# MainBoard_RASP.net
KiCad netlist of a schematic drawn in Altium Designer
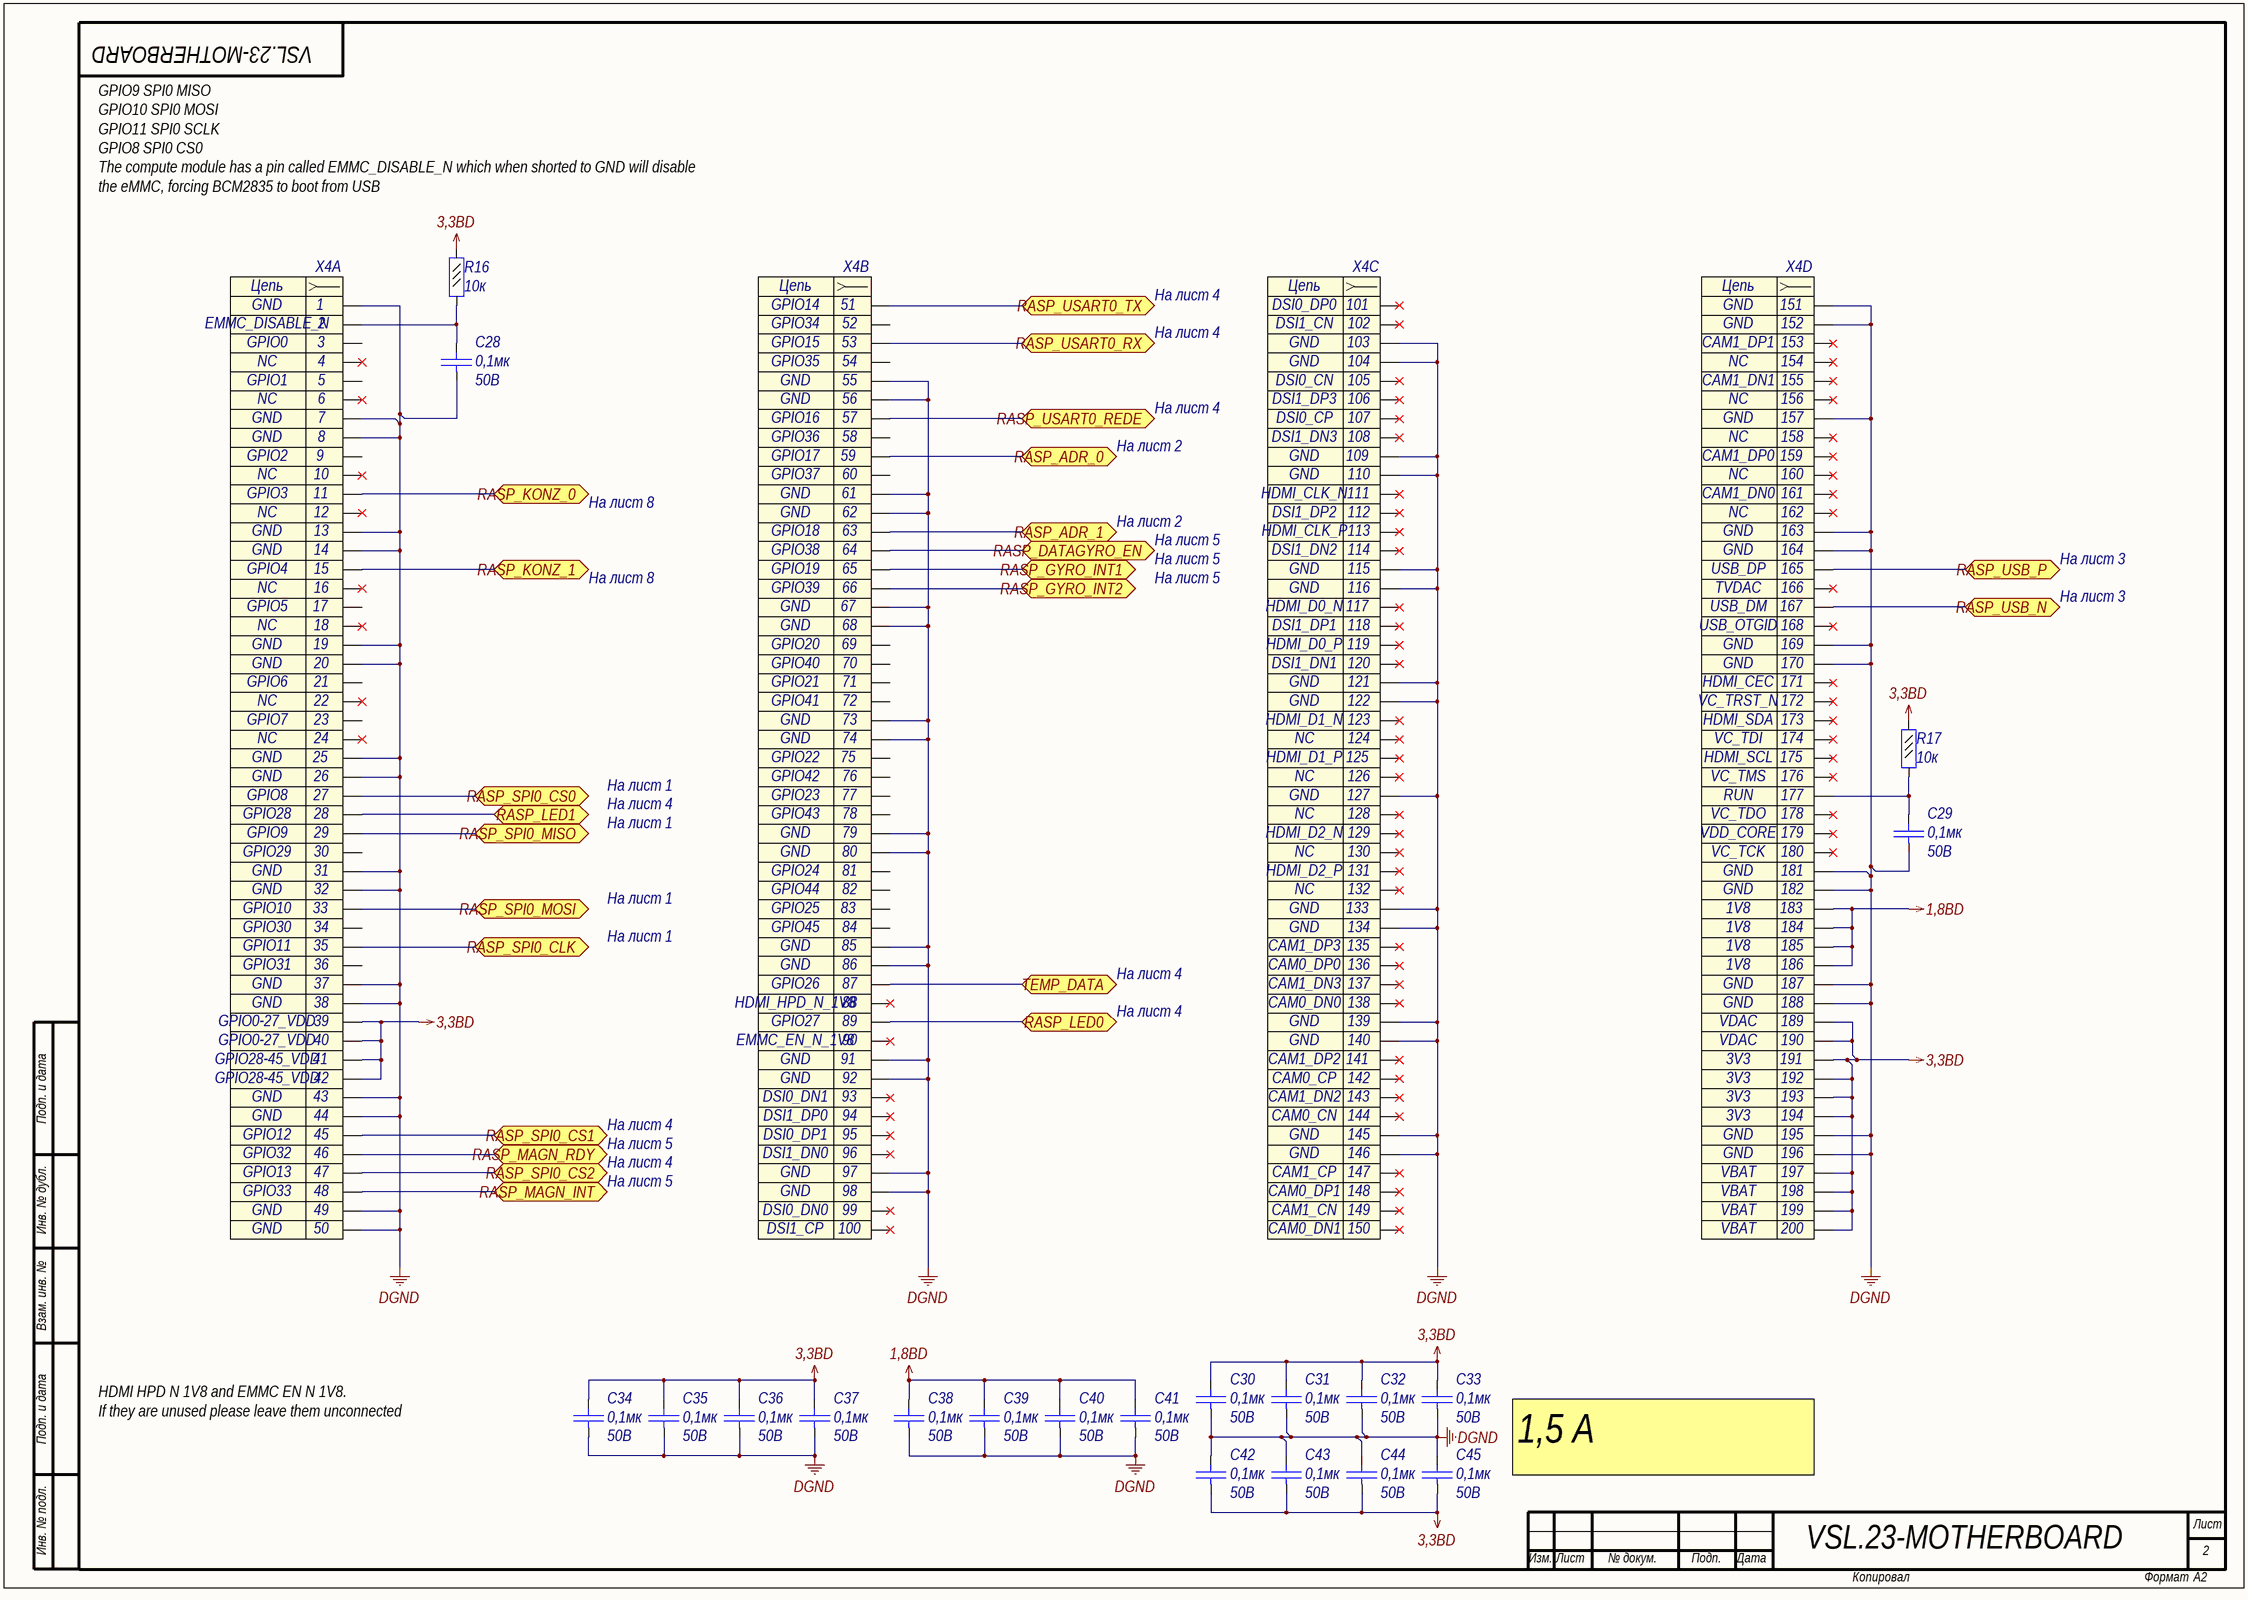
[diagram p0: MainBoard_RASP.SchDoc]

(export (version "E")
  (design (tool "Eeschema 10.0.6"))
  (components
    (comp (ref "C28")
      (value "0,1мк")
      (footprint "C0402")
      (description "Конденсатор")
      (fields
        (field (name "VOLTAGE") "50B")
        (field (name "PART NUMBER") "GRM188R71H104KA93D")
        (field (name "Comment") "Capacitor")
      )
      (libsource (lib "MOP44") (part "Capacitor"))
    )
    (comp (ref "C29")
      (value "0,1мк")
      (footprint "C0402")
      (description "Конденсатор")
      (fields
        (field (name "VOLTAGE") "50B")
        (field (name "PART NUMBER") "GRM188R71H104KA93D")
        (field (name "Comment") "Capacitor")
      )
      (libsource (lib "MOP44") (part "Capacitor"))
    )
    (comp (ref "C30")
      (value "0,1мк")
      (footprint "C0402")
      (description "Конденсатор")
      (fields
        (field (name "VOLTAGE") "50B")
        (field (name "PART NUMBER") "GRM188R71H104KA93D")
        (field (name "Comment") "Capacitor")
      )
      (libsource (lib "MOP44") (part "Capacitor"))
    )
    (comp (ref "C31")
      (value "0,1мк")
      (footprint "C0402")
      (description "Конденсатор")
      (fields
        (field (name "VOLTAGE") "50B")
        (field (name "PART NUMBER") "GRM188R71H104KA93D")
        (field (name "Comment") "Capacitor")
      )
      (libsource (lib "MOP44") (part "Capacitor"))
    )
    (comp (ref "C32")
      (value "0,1мк")
      (footprint "C0402")
      (description "Конденсатор")
      (fields
        (field (name "VOLTAGE") "50B")
        (field (name "PART NUMBER") "GRM188R71H104KA93D")
        (field (name "Comment") "Capacitor")
      )
      (libsource (lib "MOP44") (part "Capacitor"))
    )
    (comp (ref "C33")
      (value "0,1мк")
      (footprint "C0402")
      (description "Конденсатор")
      (fields
        (field (name "VOLTAGE") "50B")
        (field (name "PART NUMBER") "GRM188R71H104KA93D")
        (field (name "Comment") "Capacitor")
      )
      (libsource (lib "MOP44") (part "Capacitor"))
    )
    (comp (ref "C34")
      (value "0,1мк")
      (footprint "C0402")
      (description "Конденсатор")
      (fields
        (field (name "VOLTAGE") "50B")
        (field (name "PART NUMBER") "GRM188R71H104KA93D")
        (field (name "Comment") "Capacitor")
      )
      (libsource (lib "MOP44") (part "Capacitor"))
    )
    (comp (ref "C35")
      (value "0,1мк")
      (footprint "C0402")
      (description "Конденсатор")
      (fields
        (field (name "VOLTAGE") "50B")
        (field (name "PART NUMBER") "GRM188R71H104KA93D")
        (field (name "Comment") "Capacitor")
      )
      (libsource (lib "MOP44") (part "Capacitor"))
    )
    (comp (ref "C36")
      (value "0,1мк")
      (footprint "C0402")
      (description "Конденсатор")
      (fields
        (field (name "VOLTAGE") "50B")
        (field (name "PART NUMBER") "GRM188R71H104KA93D")
        (field (name "Comment") "Capacitor")
      )
      (libsource (lib "MOP44") (part "Capacitor"))
    )
    (comp (ref "C37")
      (value "0,1мк")
      (footprint "C0402")
      (description "Конденсатор")
      (fields
        (field (name "VOLTAGE") "50B")
        (field (name "PART NUMBER") "GRM188R71H104KA93D")
        (field (name "Comment") "Capacitor")
      )
      (libsource (lib "MOP44") (part "Capacitor"))
    )
    (comp (ref "C38")
      (value "0,1мк")
      (footprint "C0402")
      (description "Конденсатор")
      (fields
        (field (name "VOLTAGE") "50B")
        (field (name "PART NUMBER") "GRM188R71H104KA93D")
        (field (name "Comment") "Capacitor")
      )
      (libsource (lib "MOP44") (part "Capacitor"))
    )
    (comp (ref "C39")
      (value "0,1мк")
      (footprint "C0402")
      (description "Конденсатор")
      (fields
        (field (name "VOLTAGE") "50B")
        (field (name "PART NUMBER") "GRM188R71H104KA93D")
        (field (name "Comment") "Capacitor")
      )
      (libsource (lib "MOP44") (part "Capacitor"))
    )
    (comp (ref "C40")
      (value "0,1мк")
      (footprint "C0402")
      (description "Конденсатор")
      (fields
        (field (name "VOLTAGE") "50B")
        (field (name "PART NUMBER") "GRM188R71H104KA93D")
        (field (name "Comment") "Capacitor")
      )
      (libsource (lib "MOP44") (part "Capacitor"))
    )
    (comp (ref "C41")
      (value "0,1мк")
      (footprint "C0402")
      (description "Конденсатор")
      (fields
        (field (name "VOLTAGE") "50B")
        (field (name "PART NUMBER") "GRM188R71H104KA93D")
        (field (name "Comment") "Capacitor")
      )
      (libsource (lib "MOP44") (part "Capacitor"))
    )
    (comp (ref "C42")
      (value "0,1мк")
      (footprint "C0402")
      (description "Конденсатор")
      (fields
        (field (name "VOLTAGE") "50B")
        (field (name "PART NUMBER") "GRM188R71H104KA93D")
        (field (name "Comment") "Capacitor")
      )
      (libsource (lib "MOP44") (part "Capacitor"))
    )
    (comp (ref "C43")
      (value "0,1мк")
      (footprint "C0402")
      (description "Конденсатор")
      (fields
        (field (name "VOLTAGE") "50B")
        (field (name "PART NUMBER") "GRM188R71H104KA93D")
        (field (name "Comment") "Capacitor")
      )
      (libsource (lib "MOP44") (part "Capacitor"))
    )
    (comp (ref "C44")
      (value "0,1мк")
      (footprint "C0402")
      (description "Конденсатор")
      (fields
        (field (name "VOLTAGE") "50B")
        (field (name "PART NUMBER") "GRM188R71H104KA93D")
        (field (name "Comment") "Capacitor")
      )
      (libsource (lib "MOP44") (part "Capacitor"))
    )
    (comp (ref "C45")
      (value "0,1мк")
      (footprint "C0402")
      (description "Конденсатор")
      (fields
        (field (name "VOLTAGE") "50B")
        (field (name "PART NUMBER") "GRM188R71H104KA93D")
        (field (name "Comment") "Capacitor")
      )
      (libsource (lib "MOP44") (part "Capacitor"))
    )
    (comp (ref "R16")
      (value "10к")
      (footprint "R0402")
      (description "Резистор")
      (fields (field (name "PART NUMBER") "RC0402FR-0710KL") (field (name "POWER") "0,062Вт"))
      (libsource (lib "MOP44") (part "Resistor_0,062Вт"))
    )
    (comp (ref "R17")
      (value "10к")
      (footprint "R0402")
      (description "Резистор")
      (fields (field (name "PART NUMBER") "RC0402FR-0710KL") (field (name "POWER") "0,062Вт"))
      (libsource (lib "MOP44") (part "Resistor_0,062Вт"))
    )
    (comp (ref "X4")
      (value "~")
      (footprint "SODIMM 200P")
      (description "Разъем - 5 конт. розетка")
      (libsource (lib "MOP44") (part "Header_200_sct"))
    )
  )
  (nets
    (net (code "1") (name "/RASP_ADR_0") (class "Default")
      (node (ref "X4") (pin "59") (pinfunction "59_59") (pintype "passive"))
    )
    (net (code "2") (name "/RASP_ADR_1") (class "Default")
      (node (ref "X4") (pin "63") (pinfunction "63_63") (pintype "passive"))
    )
    (net (code "3") (name "/RASP_DATAGYRO_EN") (class "Default")
      (node (ref "X4") (pin "64") (pinfunction "64_64") (pintype "passive"))
    )
    (net (code "4") (name "/RASP_GYRO_INT1") (class "Default")
      (node (ref "X4") (pin "65") (pinfunction "65_65") (pintype "passive"))
    )
    (net (code "5") (name "/RASP_GYRO_INT2") (class "Default")
      (node (ref "X4") (pin "66") (pinfunction "66_66") (pintype "passive"))
    )
    (net (code "6") (name "/RASP_KONZ_0") (class "Default")
      (node (ref "X4") (pin "11") (pinfunction "11_11") (pintype "passive"))
    )
    (net (code "7") (name "/RASP_KONZ_1") (class "Default")
      (node (ref "X4") (pin "15") (pinfunction "15_15") (pintype "passive"))
    )
    (net (code "8") (name "/RASP_LED0") (class "Default")
      (node (ref "X4") (pin "89") (pinfunction "89_89") (pintype "passive"))
    )
    (net (code "9") (name "/RASP_LED1") (class "Default")
      (node (ref "X4") (pin "28") (pinfunction "28_28") (pintype "passive"))
    )
    (net (code "10") (name "/RASP_MAGN_INT") (class "Default")
      (node (ref "X4") (pin "48") (pinfunction "48_48") (pintype "passive"))
    )
    (net (code "11") (name "/RASP_MAGN_RDY") (class "Default")
      (node (ref "X4") (pin "46") (pinfunction "46_46") (pintype "passive"))
    )
    (net (code "12") (name "/RASP_SPI0_CLK") (class "Default")
      (node (ref "X4") (pin "35") (pinfunction "35_35") (pintype "passive"))
    )
    (net (code "13") (name "/RASP_SPI0_CS0") (class "Default")
      (node (ref "X4") (pin "27") (pinfunction "27_27") (pintype "passive"))
    )
    (net (code "14") (name "/RASP_SPI0_CS1") (class "Default")
      (node (ref "X4") (pin "45") (pinfunction "45_45") (pintype "passive"))
    )
    (net (code "15") (name "/RASP_SPI0_CS2") (class "Default")
      (node (ref "X4") (pin "47") (pinfunction "47_47") (pintype "passive"))
    )
    (net (code "16") (name "/RASP_SPI0_MISO") (class "Default")
      (node (ref "X4") (pin "29") (pinfunction "29_29") (pintype "passive"))
    )
    (net (code "17") (name "/RASP_SPI0_MOSI") (class "Default")
      (node (ref "X4") (pin "33") (pinfunction "33_33") (pintype "passive"))
    )
    (net (code "18") (name "/RASP_USART0_REDE") (class "Default")
      (node (ref "X4") (pin "57") (pinfunction "57_57") (pintype "passive"))
    )
    (net (code "19") (name "/RASP_USART0_RX") (class "Default")
      (node (ref "X4") (pin "53") (pinfunction "53_53") (pintype "passive"))
    )
    (net (code "20") (name "/RASP_USART0_TX") (class "Default")
      (node (ref "X4") (pin "51") (pinfunction "51_51") (pintype "passive"))
    )
    (net (code "21") (name "/RASP_USB_N") (class "Default")
      (node (ref "X4") (pin "167") (pinfunction "167_167") (pintype "passive"))
    )
    (net (code "22") (name "/RASP_USB_P") (class "Default")
      (node (ref "X4") (pin "165") (pinfunction "165_165") (pintype "passive"))
    )
    (net (code "23") (name "/TEMP_DATA") (class "Default")
      (node (ref "X4") (pin "87") (pinfunction "87_87") (pintype "passive"))
    )
    (net (code "24") (name "1,8BD") (class "Default")
      (node (ref "C38") (pin "2") (pinfunction "2_2") (pintype "passive"))
      (node (ref "C39") (pin "2") (pinfunction "2_2") (pintype "passive"))
      (node (ref "C40") (pin "2") (pinfunction "2_2") (pintype "passive"))
      (node (ref "C41") (pin "2") (pinfunction "2_2") (pintype "passive"))
      (node (ref "X4") (pin "183") (pinfunction "183_183") (pintype "passive"))
      (node (ref "X4") (pin "184") (pinfunction "184_184") (pintype "passive"))
      (node (ref "X4") (pin "185") (pinfunction "185_185") (pintype "passive"))
      (node (ref "X4") (pin "186") (pinfunction "186_186") (pintype "passive"))
    )
    (net (code "25") (name "3,3BD") (class "Default")
      (node (ref "C30") (pin "2") (pinfunction "2_2") (pintype "passive"))
      (node (ref "C31") (pin "2") (pinfunction "2_2") (pintype "passive"))
      (node (ref "C32") (pin "2") (pinfunction "2_2") (pintype "passive"))
      (node (ref "C33") (pin "2") (pinfunction "2_2") (pintype "passive"))
      (node (ref "C34") (pin "2") (pinfunction "2_2") (pintype "passive"))
      (node (ref "C35") (pin "2") (pinfunction "2_2") (pintype "passive"))
      (node (ref "C36") (pin "2") (pinfunction "2_2") (pintype "passive"))
      (node (ref "C37") (pin "2") (pinfunction "2_2") (pintype "passive"))
      (node (ref "C42") (pin "1") (pinfunction "1_1") (pintype "passive"))
      (node (ref "C43") (pin "1") (pinfunction "1_1") (pintype "passive"))
      (node (ref "C44") (pin "1") (pinfunction "1_1") (pintype "passive"))
      (node (ref "C45") (pin "1") (pinfunction "1_1") (pintype "passive"))
      (node (ref "R16") (pin "1") (pinfunction "1_1") (pintype "passive"))
      (node (ref "R17") (pin "1") (pinfunction "1_1") (pintype "passive"))
      (node (ref "X4") (pin "189") (pinfunction "189_189") (pintype "passive"))
      (node (ref "X4") (pin "190") (pinfunction "190_190") (pintype "passive"))
      (node (ref "X4") (pin "191") (pinfunction "191_191") (pintype "passive"))
      (node (ref "X4") (pin "192") (pinfunction "192_192") (pintype "passive"))
      (node (ref "X4") (pin "193") (pinfunction "193_193") (pintype "passive"))
      (node (ref "X4") (pin "194") (pinfunction "194_194") (pintype "passive"))
      (node (ref "X4") (pin "197") (pinfunction "197_197") (pintype "passive"))
      (node (ref "X4") (pin "198") (pinfunction "198_198") (pintype "passive"))
      (node (ref "X4") (pin "199") (pinfunction "199_199") (pintype "passive"))
      (node (ref "X4") (pin "200") (pinfunction "200_200") (pintype "passive"))
      (node (ref "X4") (pin "39") (pinfunction "39_39") (pintype "passive"))
      (node (ref "X4") (pin "40") (pinfunction "40_40") (pintype "passive"))
      (node (ref "X4") (pin "41") (pinfunction "41_41") (pintype "passive"))
      (node (ref "X4") (pin "42") (pinfunction "42_42") (pintype "passive"))
    )
    (net (code "26") (name "DGND") (class "Default")
      (node (ref "C28") (pin "1") (pinfunction "1_1") (pintype "passive"))
      (node (ref "C29") (pin "1") (pinfunction "1_1") (pintype "passive"))
      (node (ref "C30") (pin "1") (pinfunction "1_1") (pintype "passive"))
      (node (ref "C31") (pin "1") (pinfunction "1_1") (pintype "passive"))
      (node (ref "C32") (pin "1") (pinfunction "1_1") (pintype "passive"))
      (node (ref "C33") (pin "1") (pinfunction "1_1") (pintype "passive"))
      (node (ref "C34") (pin "1") (pinfunction "1_1") (pintype "passive"))
      (node (ref "C35") (pin "1") (pinfunction "1_1") (pintype "passive"))
      (node (ref "C36") (pin "1") (pinfunction "1_1") (pintype "passive"))
      (node (ref "C37") (pin "1") (pinfunction "1_1") (pintype "passive"))
      (node (ref "C38") (pin "1") (pinfunction "1_1") (pintype "passive"))
      (node (ref "C39") (pin "1") (pinfunction "1_1") (pintype "passive"))
      (node (ref "C40") (pin "1") (pinfunction "1_1") (pintype "passive"))
      (node (ref "C41") (pin "1") (pinfunction "1_1") (pintype "passive"))
      (node (ref "C42") (pin "2") (pinfunction "2_2") (pintype "passive"))
      (node (ref "C43") (pin "2") (pinfunction "2_2") (pintype "passive"))
      (node (ref "C44") (pin "2") (pinfunction "2_2") (pintype "passive"))
      (node (ref "C45") (pin "2") (pinfunction "2_2") (pintype "passive"))
      (node (ref "X4") (pin "1") (pinfunction "1_1") (pintype "passive"))
      (node (ref "X4") (pin "103") (pinfunction "103_103") (pintype "passive"))
      (node (ref "X4") (pin "104") (pinfunction "104_104") (pintype "passive"))
      (node (ref "X4") (pin "109") (pinfunction "109_109") (pintype "passive"))
      (node (ref "X4") (pin "110") (pinfunction "110_110") (pintype "passive"))
      (node (ref "X4") (pin "115") (pinfunction "115_115") (pintype "passive"))
      (node (ref "X4") (pin "116") (pinfunction "116_116") (pintype "passive"))
      (node (ref "X4") (pin "121") (pinfunction "121_121") (pintype "passive"))
      (node (ref "X4") (pin "122") (pinfunction "122_122") (pintype "passive"))
      (node (ref "X4") (pin "127") (pinfunction "127_127") (pintype "passive"))
      (node (ref "X4") (pin "13") (pinfunction "13_13") (pintype "passive"))
      (node (ref "X4") (pin "133") (pinfunction "133_133") (pintype "passive"))
      (node (ref "X4") (pin "134") (pinfunction "134_134") (pintype "passive"))
      (node (ref "X4") (pin "139") (pinfunction "139_139") (pintype "passive"))
      (node (ref "X4") (pin "14") (pinfunction "14_14") (pintype "passive"))
      (node (ref "X4") (pin "140") (pinfunction "140_140") (pintype "passive"))
      (node (ref "X4") (pin "145") (pinfunction "145_145") (pintype "passive"))
      (node (ref "X4") (pin "146") (pinfunction "146_146") (pintype "passive"))
      (node (ref "X4") (pin "151") (pinfunction "151_151") (pintype "passive"))
      (node (ref "X4") (pin "152") (pinfunction "152_152") (pintype "passive"))
      (node (ref "X4") (pin "157") (pinfunction "157_157") (pintype "passive"))
      (node (ref "X4") (pin "163") (pinfunction "163_163") (pintype "passive"))
      (node (ref "X4") (pin "164") (pinfunction "164_164") (pintype "passive"))
      (node (ref "X4") (pin "169") (pinfunction "169_169") (pintype "passive"))
      (node (ref "X4") (pin "170") (pinfunction "170_170") (pintype "passive"))
      (node (ref "X4") (pin "181") (pinfunction "181_181") (pintype "passive"))
      (node (ref "X4") (pin "182") (pinfunction "182_182") (pintype "passive"))
      (node (ref "X4") (pin "187") (pinfunction "187_187") (pintype "passive"))
      (node (ref "X4") (pin "188") (pinfunction "188_188") (pintype "passive"))
      (node (ref "X4") (pin "19") (pinfunction "19_19") (pintype "passive"))
      (node (ref "X4") (pin "195") (pinfunction "195_195") (pintype "passive"))
      (node (ref "X4") (pin "196") (pinfunction "196_196") (pintype "passive"))
      (node (ref "X4") (pin "20") (pinfunction "20_20") (pintype "passive"))
      (node (ref "X4") (pin "25") (pinfunction "25_25") (pintype "passive"))
      (node (ref "X4") (pin "26") (pinfunction "26_26") (pintype "passive"))
      (node (ref "X4") (pin "31") (pinfunction "31_31") (pintype "passive"))
      (node (ref "X4") (pin "32") (pinfunction "32_32") (pintype "passive"))
      (node (ref "X4") (pin "37") (pinfunction "37_37") (pintype "passive"))
      (node (ref "X4") (pin "38") (pinfunction "38_38") (pintype "passive"))
      (node (ref "X4") (pin "43") (pinfunction "43_43") (pintype "passive"))
      (node (ref "X4") (pin "44") (pinfunction "44_44") (pintype "passive"))
      (node (ref "X4") (pin "49") (pinfunction "49_49") (pintype "passive"))
      (node (ref "X4") (pin "50") (pinfunction "50_50") (pintype "passive"))
      (node (ref "X4") (pin "55") (pinfunction "55_55") (pintype "passive"))
      (node (ref "X4") (pin "56") (pinfunction "56_56") (pintype "passive"))
      (node (ref "X4") (pin "61") (pinfunction "61_61") (pintype "passive"))
      (node (ref "X4") (pin "62") (pinfunction "62_62") (pintype "passive"))
      (node (ref "X4") (pin "67") (pinfunction "67_67") (pintype "passive"))
      (node (ref "X4") (pin "68") (pinfunction "68_68") (pintype "passive"))
      (node (ref "X4") (pin "7") (pinfunction "7_7") (pintype "passive"))
      (node (ref "X4") (pin "73") (pinfunction "73_73") (pintype "passive"))
      (node (ref "X4") (pin "74") (pinfunction "74_74") (pintype "passive"))
      (node (ref "X4") (pin "79") (pinfunction "79_79") (pintype "passive"))
      (node (ref "X4") (pin "8") (pinfunction "8_8") (pintype "passive"))
      (node (ref "X4") (pin "80") (pinfunction "80_80") (pintype "passive"))
      (node (ref "X4") (pin "85") (pinfunction "85_85") (pintype "passive"))
      (node (ref "X4") (pin "86") (pinfunction "86_86") (pintype "passive"))
      (node (ref "X4") (pin "91") (pinfunction "91_91") (pintype "passive"))
      (node (ref "X4") (pin "92") (pinfunction "92_92") (pintype "passive"))
      (node (ref "X4") (pin "97") (pinfunction "97_97") (pintype "passive"))
      (node (ref "X4") (pin "98") (pinfunction "98_98") (pintype "passive"))
    )
    (net (code "27") (name "Net-(C28-Pad2)") (class "Default")
      (node (ref "C28") (pin "2") (pinfunction "2_2") (pintype "passive"))
      (node (ref "R16") (pin "2") (pinfunction "2_2") (pintype "passive"))
      (node (ref "X4") (pin "2") (pinfunction "2_2") (pintype "passive"))
    )
    (net (code "28") (name "Net-(C29-Pad2)") (class "Default")
      (node (ref "C29") (pin "2") (pinfunction "2_2") (pintype "passive"))
      (node (ref "R17") (pin "2") (pinfunction "2_2") (pintype "passive"))
      (node (ref "X4") (pin "177") (pinfunction "177_177") (pintype "passive"))
    )
    (net (code "29") (name "unconnected-(X4-Pad3)") (class "Default")
      (node (ref "X4") (pin "3") (pinfunction "3_3") (pintype "passive"))
    )
    (net (code "30") (name "unconnected-(X4-Pad4)") (class "Default")
      (node (ref "X4") (pin "4") (pinfunction "4_4") (pintype "passive+no_connect"))
    )
    (net (code "31") (name "unconnected-(X4-Pad5)") (class "Default")
      (node (ref "X4") (pin "5") (pinfunction "5_5") (pintype "passive"))
    )
    (net (code "32") (name "unconnected-(X4-Pad6)") (class "Default")
      (node (ref "X4") (pin "6") (pinfunction "6_6") (pintype "passive+no_connect"))
    )
    (net (code "33") (name "unconnected-(X4-Pad9)") (class "Default")
      (node (ref "X4") (pin "9") (pinfunction "9_9") (pintype "passive"))
    )
    (net (code "34") (name "unconnected-(X4-Pad10)") (class "Default")
      (node (ref "X4") (pin "10") (pinfunction "10_10") (pintype "passive+no_connect"))
    )
    (net (code "35") (name "unconnected-(X4-Pad12)") (class "Default")
      (node (ref "X4") (pin "12") (pinfunction "12_12") (pintype "passive+no_connect"))
    )
    (net (code "36") (name "unconnected-(X4-Pad16)") (class "Default")
      (node (ref "X4") (pin "16") (pinfunction "16_16") (pintype "passive+no_connect"))
    )
    (net (code "37") (name "unconnected-(X4-Pad17)") (class "Default")
      (node (ref "X4") (pin "17") (pinfunction "17_17") (pintype "passive"))
    )
    (net (code "38") (name "unconnected-(X4-Pad18)") (class "Default")
      (node (ref "X4") (pin "18") (pinfunction "18_18") (pintype "passive+no_connect"))
    )
    (net (code "39") (name "unconnected-(X4-Pad21)") (class "Default")
      (node (ref "X4") (pin "21") (pinfunction "21_21") (pintype "passive"))
    )
    (net (code "40") (name "unconnected-(X4-Pad22)") (class "Default")
      (node (ref "X4") (pin "22") (pinfunction "22_22") (pintype "passive+no_connect"))
    )
    (net (code "41") (name "unconnected-(X4-Pad23)") (class "Default")
      (node (ref "X4") (pin "23") (pinfunction "23_23") (pintype "passive"))
    )
    (net (code "42") (name "unconnected-(X4-Pad24)") (class "Default")
      (node (ref "X4") (pin "24") (pinfunction "24_24") (pintype "passive+no_connect"))
    )
    (net (code "43") (name "unconnected-(X4-Pad30)") (class "Default")
      (node (ref "X4") (pin "30") (pinfunction "30_30") (pintype "passive"))
    )
    (net (code "44") (name "unconnected-(X4-Pad34)") (class "Default")
      (node (ref "X4") (pin "34") (pinfunction "34_34") (pintype "passive"))
    )
    (net (code "45") (name "unconnected-(X4-Pad36)") (class "Default")
      (node (ref "X4") (pin "36") (pinfunction "36_36") (pintype "passive"))
    )
    (net (code "46") (name "unconnected-(X4-Pad52)") (class "Default")
      (node (ref "X4") (pin "52") (pinfunction "52_52") (pintype "passive"))
    )
    (net (code "47") (name "unconnected-(X4-Pad54)") (class "Default")
      (node (ref "X4") (pin "54") (pinfunction "54_54") (pintype "passive"))
    )
    (net (code "48") (name "unconnected-(X4-Pad58)") (class "Default")
      (node (ref "X4") (pin "58") (pinfunction "58_58") (pintype "passive"))
    )
    (net (code "49") (name "unconnected-(X4-Pad60)") (class "Default")
      (node (ref "X4") (pin "60") (pinfunction "60_60") (pintype "passive"))
    )
    (net (code "50") (name "unconnected-(X4-Pad69)") (class "Default")
      (node (ref "X4") (pin "69") (pinfunction "69_69") (pintype "passive"))
    )
    (net (code "51") (name "unconnected-(X4-Pad70)") (class "Default")
      (node (ref "X4") (pin "70") (pinfunction "70_70") (pintype "passive"))
    )
    (net (code "52") (name "unconnected-(X4-Pad71)") (class "Default")
      (node (ref "X4") (pin "71") (pinfunction "71_71") (pintype "passive"))
    )
    (net (code "53") (name "unconnected-(X4-Pad72)") (class "Default")
      (node (ref "X4") (pin "72") (pinfunction "72_72") (pintype "passive"))
    )
    (net (code "54") (name "unconnected-(X4-Pad75)") (class "Default")
      (node (ref "X4") (pin "75") (pinfunction "75_75") (pintype "passive"))
    )
    (net (code "55") (name "unconnected-(X4-Pad76)") (class "Default")
      (node (ref "X4") (pin "76") (pinfunction "76_76") (pintype "passive"))
    )
    (net (code "56") (name "unconnected-(X4-Pad77)") (class "Default")
      (node (ref "X4") (pin "77") (pinfunction "77_77") (pintype "passive"))
    )
    (net (code "57") (name "unconnected-(X4-Pad78)") (class "Default")
      (node (ref "X4") (pin "78") (pinfunction "78_78") (pintype "passive"))
    )
    (net (code "58") (name "unconnected-(X4-Pad81)") (class "Default")
      (node (ref "X4") (pin "81") (pinfunction "81_81") (pintype "passive"))
    )
    (net (code "59") (name "unconnected-(X4-Pad82)") (class "Default")
      (node (ref "X4") (pin "82") (pinfunction "82_82") (pintype "passive"))
    )
    (net (code "60") (name "unconnected-(X4-Pad83)") (class "Default")
      (node (ref "X4") (pin "83") (pinfunction "83_83") (pintype "passive"))
    )
    (net (code "61") (name "unconnected-(X4-Pad84)") (class "Default")
      (node (ref "X4") (pin "84") (pinfunction "84_84") (pintype "passive"))
    )
    (net (code "62") (name "unconnected-(X4-Pad88)") (class "Default")
      (node (ref "X4") (pin "88") (pinfunction "88_88") (pintype "passive+no_connect"))
    )
    (net (code "63") (name "unconnected-(X4-Pad90)") (class "Default")
      (node (ref "X4") (pin "90") (pinfunction "90_90") (pintype "passive+no_connect"))
    )
    (net (code "64") (name "unconnected-(X4-Pad93)") (class "Default")
      (node (ref "X4") (pin "93") (pinfunction "93_93") (pintype "passive+no_connect"))
    )
    (net (code "65") (name "unconnected-(X4-Pad94)") (class "Default")
      (node (ref "X4") (pin "94") (pinfunction "94_94") (pintype "passive+no_connect"))
    )
    (net (code "66") (name "unconnected-(X4-Pad95)") (class "Default")
      (node (ref "X4") (pin "95") (pinfunction "95_95") (pintype "passive+no_connect"))
    )
    (net (code "67") (name "unconnected-(X4-Pad96)") (class "Default")
      (node (ref "X4") (pin "96") (pinfunction "96_96") (pintype "passive+no_connect"))
    )
    (net (code "68") (name "unconnected-(X4-Pad99)") (class "Default")
      (node (ref "X4") (pin "99") (pinfunction "99_99") (pintype "passive+no_connect"))
    )
    (net (code "69") (name "unconnected-(X4-Pad100)") (class "Default")
      (node (ref "X4") (pin "100") (pinfunction "100_100") (pintype "passive+no_connect"))
    )
    (net (code "70") (name "unconnected-(X4-Pad101)") (class "Default")
      (node (ref "X4") (pin "101") (pinfunction "101_101") (pintype "passive+no_connect"))
    )
    (net (code "71") (name "unconnected-(X4-Pad102)") (class "Default")
      (node (ref "X4") (pin "102") (pinfunction "102_102") (pintype "passive+no_connect"))
    )
    (net (code "72") (name "unconnected-(X4-Pad105)") (class "Default")
      (node (ref "X4") (pin "105") (pinfunction "105_105") (pintype "passive+no_connect"))
    )
    (net (code "73") (name "unconnected-(X4-Pad106)") (class "Default")
      (node (ref "X4") (pin "106") (pinfunction "106_106") (pintype "passive+no_connect"))
    )
    (net (code "74") (name "unconnected-(X4-Pad107)") (class "Default")
      (node (ref "X4") (pin "107") (pinfunction "107_107") (pintype "passive+no_connect"))
    )
    (net (code "75") (name "unconnected-(X4-Pad108)") (class "Default")
      (node (ref "X4") (pin "108") (pinfunction "108_108") (pintype "passive+no_connect"))
    )
    (net (code "76") (name "unconnected-(X4-Pad111)") (class "Default")
      (node (ref "X4") (pin "111") (pinfunction "111_111") (pintype "passive+no_connect"))
    )
    (net (code "77") (name "unconnected-(X4-Pad112)") (class "Default")
      (node (ref "X4") (pin "112") (pinfunction "112_112") (pintype "passive+no_connect"))
    )
    (net (code "78") (name "unconnected-(X4-Pad113)") (class "Default")
      (node (ref "X4") (pin "113") (pinfunction "113_113") (pintype "passive+no_connect"))
    )
    (net (code "79") (name "unconnected-(X4-Pad114)") (class "Default")
      (node (ref "X4") (pin "114") (pinfunction "114_114") (pintype "passive+no_connect"))
    )
    (net (code "80") (name "unconnected-(X4-Pad117)") (class "Default")
      (node (ref "X4") (pin "117") (pinfunction "117_117") (pintype "passive+no_connect"))
    )
    (net (code "81") (name "unconnected-(X4-Pad118)") (class "Default")
      (node (ref "X4") (pin "118") (pinfunction "118_118") (pintype "passive+no_connect"))
    )
    (net (code "82") (name "unconnected-(X4-Pad119)") (class "Default")
      (node (ref "X4") (pin "119") (pinfunction "119_119") (pintype "passive+no_connect"))
    )
    (net (code "83") (name "unconnected-(X4-Pad120)") (class "Default")
      (node (ref "X4") (pin "120") (pinfunction "120_120") (pintype "passive+no_connect"))
    )
    (net (code "84") (name "unconnected-(X4-Pad123)") (class "Default")
      (node (ref "X4") (pin "123") (pinfunction "123_123") (pintype "passive+no_connect"))
    )
    (net (code "85") (name "unconnected-(X4-Pad124)") (class "Default")
      (node (ref "X4") (pin "124") (pinfunction "124_124") (pintype "passive+no_connect"))
    )
    (net (code "86") (name "unconnected-(X4-Pad125)") (class "Default")
      (node (ref "X4") (pin "125") (pinfunction "125_125") (pintype "passive+no_connect"))
    )
    (net (code "87") (name "unconnected-(X4-Pad126)") (class "Default")
      (node (ref "X4") (pin "126") (pinfunction "126_126") (pintype "passive+no_connect"))
    )
    (net (code "88") (name "unconnected-(X4-Pad128)") (class "Default")
      (node (ref "X4") (pin "128") (pinfunction "128_128") (pintype "passive+no_connect"))
    )
    (net (code "89") (name "unconnected-(X4-Pad129)") (class "Default")
      (node (ref "X4") (pin "129") (pinfunction "129_129") (pintype "passive+no_connect"))
    )
    (net (code "90") (name "unconnected-(X4-Pad130)") (class "Default")
      (node (ref "X4") (pin "130") (pinfunction "130_130") (pintype "passive+no_connect"))
    )
    (net (code "91") (name "unconnected-(X4-Pad131)") (class "Default")
      (node (ref "X4") (pin "131") (pinfunction "131_131") (pintype "passive+no_connect"))
    )
    (net (code "92") (name "unconnected-(X4-Pad132)") (class "Default")
      (node (ref "X4") (pin "132") (pinfunction "132_132") (pintype "passive+no_connect"))
    )
    (net (code "93") (name "unconnected-(X4-Pad135)") (class "Default")
      (node (ref "X4") (pin "135") (pinfunction "135_135") (pintype "passive+no_connect"))
    )
    (net (code "94") (name "unconnected-(X4-Pad136)") (class "Default")
      (node (ref "X4") (pin "136") (pinfunction "136_136") (pintype "passive+no_connect"))
    )
    (net (code "95") (name "unconnected-(X4-Pad137)") (class "Default")
      (node (ref "X4") (pin "137") (pinfunction "137_137") (pintype "passive+no_connect"))
    )
    (net (code "96") (name "unconnected-(X4-Pad138)") (class "Default")
      (node (ref "X4") (pin "138") (pinfunction "138_138") (pintype "passive+no_connect"))
    )
    (net (code "97") (name "unconnected-(X4-Pad141)") (class "Default")
      (node (ref "X4") (pin "141") (pinfunction "141_141") (pintype "passive+no_connect"))
    )
    (net (code "98") (name "unconnected-(X4-Pad142)") (class "Default")
      (node (ref "X4") (pin "142") (pinfunction "142_142") (pintype "passive+no_connect"))
    )
    (net (code "99") (name "unconnected-(X4-Pad143)") (class "Default")
      (node (ref "X4") (pin "143") (pinfunction "143_143") (pintype "passive+no_connect"))
    )
    (net (code "100") (name "unconnected-(X4-Pad144)") (class "Default")
      (node (ref "X4") (pin "144") (pinfunction "144_144") (pintype "passive+no_connect"))
    )
    (net (code "101") (name "unconnected-(X4-Pad147)") (class "Default")
      (node (ref "X4") (pin "147") (pinfunction "147_147") (pintype "passive+no_connect"))
    )
    (net (code "102") (name "unconnected-(X4-Pad148)") (class "Default")
      (node (ref "X4") (pin "148") (pinfunction "148_148") (pintype "passive+no_connect"))
    )
    (net (code "103") (name "unconnected-(X4-Pad149)") (class "Default")
      (node (ref "X4") (pin "149") (pinfunction "149_149") (pintype "passive+no_connect"))
    )
    (net (code "104") (name "unconnected-(X4-Pad150)") (class "Default")
      (node (ref "X4") (pin "150") (pinfunction "150_150") (pintype "passive+no_connect"))
    )
    (net (code "105") (name "unconnected-(X4-Pad153)") (class "Default")
      (node (ref "X4") (pin "153") (pinfunction "153_153") (pintype "passive+no_connect"))
    )
    (net (code "106") (name "unconnected-(X4-Pad154)") (class "Default")
      (node (ref "X4") (pin "154") (pinfunction "154_154") (pintype "passive+no_connect"))
    )
    (net (code "107") (name "unconnected-(X4-Pad155)") (class "Default")
      (node (ref "X4") (pin "155") (pinfunction "155_155") (pintype "passive+no_connect"))
    )
    (net (code "108") (name "unconnected-(X4-Pad156)") (class "Default")
      (node (ref "X4") (pin "156") (pinfunction "156_156") (pintype "passive+no_connect"))
    )
    (net (code "109") (name "unconnected-(X4-Pad158)") (class "Default")
      (node (ref "X4") (pin "158") (pinfunction "158_158") (pintype "passive+no_connect"))
    )
    (net (code "110") (name "unconnected-(X4-Pad159)") (class "Default")
      (node (ref "X4") (pin "159") (pinfunction "159_159") (pintype "passive+no_connect"))
    )
    (net (code "111") (name "unconnected-(X4-Pad160)") (class "Default")
      (node (ref "X4") (pin "160") (pinfunction "160_160") (pintype "passive+no_connect"))
    )
    (net (code "112") (name "unconnected-(X4-Pad161)") (class "Default")
      (node (ref "X4") (pin "161") (pinfunction "161_161") (pintype "passive+no_connect"))
    )
    (net (code "113") (name "unconnected-(X4-Pad162)") (class "Default")
      (node (ref "X4") (pin "162") (pinfunction "162_162") (pintype "passive+no_connect"))
    )
    (net (code "114") (name "unconnected-(X4-Pad166)") (class "Default")
      (node (ref "X4") (pin "166") (pinfunction "166_166") (pintype "passive+no_connect"))
    )
    (net (code "115") (name "unconnected-(X4-Pad168)") (class "Default")
      (node (ref "X4") (pin "168") (pinfunction "168_168") (pintype "passive+no_connect"))
    )
    (net (code "116") (name "unconnected-(X4-Pad171)") (class "Default")
      (node (ref "X4") (pin "171") (pinfunction "171_171") (pintype "passive+no_connect"))
    )
    (net (code "117") (name "unconnected-(X4-Pad172)") (class "Default")
      (node (ref "X4") (pin "172") (pinfunction "172_172") (pintype "passive+no_connect"))
    )
    (net (code "118") (name "unconnected-(X4-Pad173)") (class "Default")
      (node (ref "X4") (pin "173") (pinfunction "173_173") (pintype "passive+no_connect"))
    )
    (net (code "119") (name "unconnected-(X4-Pad174)") (class "Default")
      (node (ref "X4") (pin "174") (pinfunction "174_174") (pintype "passive+no_connect"))
    )
    (net (code "120") (name "unconnected-(X4-Pad175)") (class "Default")
      (node (ref "X4") (pin "175") (pinfunction "175_175") (pintype "passive+no_connect"))
    )
    (net (code "121") (name "unconnected-(X4-Pad176)") (class "Default")
      (node (ref "X4") (pin "176") (pinfunction "176_176") (pintype "passive+no_connect"))
    )
    (net (code "122") (name "unconnected-(X4-Pad178)") (class "Default")
      (node (ref "X4") (pin "178") (pinfunction "178_178") (pintype "passive+no_connect"))
    )
    (net (code "123") (name "unconnected-(X4-Pad179)") (class "Default")
      (node (ref "X4") (pin "179") (pinfunction "179_179") (pintype "passive+no_connect"))
    )
    (net (code "124") (name "unconnected-(X4-Pad180)") (class "Default")
      (node (ref "X4") (pin "180") (pinfunction "180_180") (pintype "passive+no_connect"))
    )
  )
)
